# universky-SENSOR.net
KiCad netlist of a schematic drawn in Altium Designer
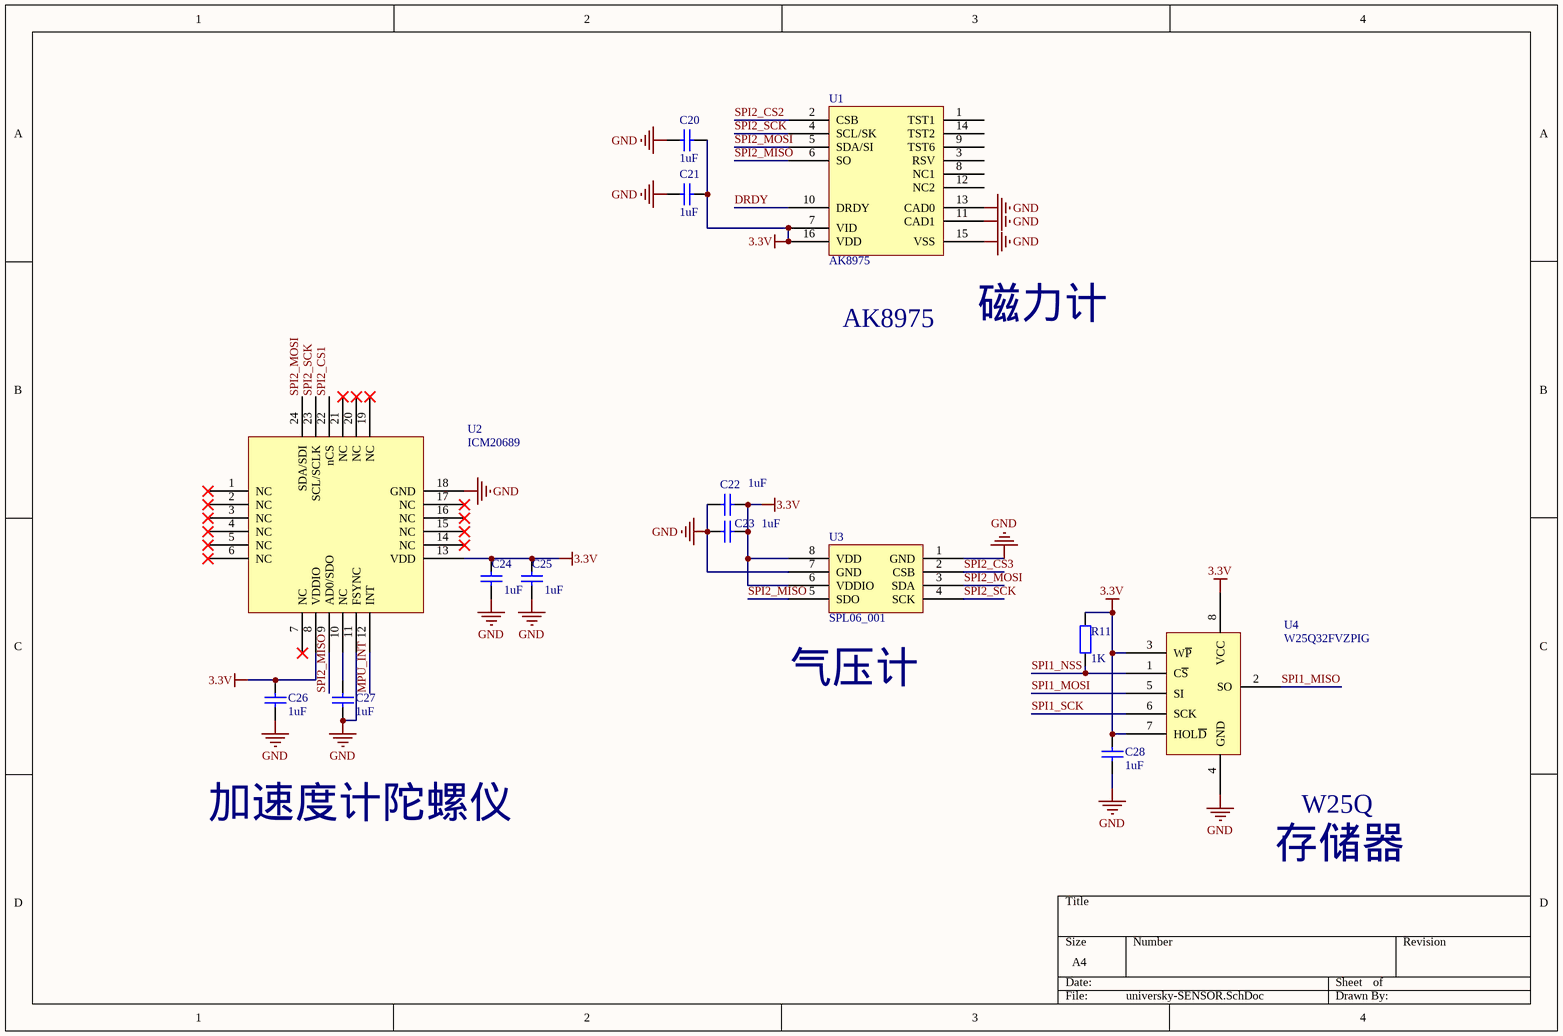
[diagram p0: universky-SENSOR.SchDoc]

(export (version "E")
  (design (tool "Eeschema 10.0.6"))
  (components
    (comp (ref "C20")
      (value "1uF")
      (footprint "0603_C")
      (description "Capacitor")
      (fields (field (name "Comment") "Cap") (field (name "PUBLISHER") "Altium Limited"))
      (libsource (lib "Miscellaneous Devices") (part "Cap"))
    )
    (comp (ref "C21")
      (value "1uF")
      (footprint "0603_C")
      (description "Capacitor")
      (fields (field (name "Comment") "Cap") (field (name "PUBLISHER") "Altium Limited"))
      (libsource (lib "Miscellaneous Devices") (part "Cap"))
    )
    (comp (ref "C22")
      (value "1uF")
      (footprint "0603_C")
      (description "Capacitor")
      (fields (field (name "Comment") "Cap") (field (name "PUBLISHER") "Altium Limited"))
      (libsource (lib "Miscellaneous Devices") (part "Cap"))
    )
    (comp (ref "C23")
      (value "1uF")
      (footprint "0603_C")
      (description "Capacitor")
      (fields (field (name "Comment") "Cap") (field (name "PUBLISHER") "Altium Limited"))
      (libsource (lib "Miscellaneous Devices") (part "Cap"))
    )
    (comp (ref "C24")
      (value "1uF")
      (footprint "0603_C")
      (description "Capacitor")
      (fields (field (name "Comment") "Cap") (field (name "PUBLISHER") "Altium Limited"))
      (libsource (lib "Miscellaneous Devices") (part "Cap"))
    )
    (comp (ref "C25")
      (value "1uF")
      (footprint "0603_C")
      (description "Capacitor")
      (fields (field (name "Comment") "Cap") (field (name "PUBLISHER") "Altium Limited"))
      (libsource (lib "Miscellaneous Devices") (part "Cap"))
    )
    (comp (ref "C26")
      (value "1uF")
      (footprint "0603_C")
      (description "Capacitor")
      (fields (field (name "Comment") "Cap") (field (name "PUBLISHER") "Altium Limited"))
      (libsource (lib "Miscellaneous Devices") (part "Cap"))
    )
    (comp (ref "C27")
      (value "1uF")
      (footprint "0603_C")
      (description "Capacitor")
      (fields (field (name "Comment") "Cap") (field (name "PUBLISHER") "Altium Limited"))
      (libsource (lib "Miscellaneous Devices") (part "Cap"))
    )
    (comp (ref "C28")
      (value "1uF")
      (footprint "0603_C")
      (description "Capacitor")
      (fields (field (name "Comment") "Cap") (field (name "PUBLISHER") "Altium Limited"))
      (libsource (lib "Miscellaneous Devices") (part "Cap"))
    )
    (comp (ref "R11")
      (value "1K")
      (footprint "0603_R")
      (description "Resistor")
      (fields (field (name "Comment") "Res2") (field (name "PUBLISHER") "Altium Limited"))
      (libsource (lib "Miscellaneous Devices") (part "Res2"))
    )
    (comp (ref "U1") (value "AK8975") (footprint "QFN_16") (libsource (lib "dx原理图库") (part "AK8975")))
    (comp (ref "U2") (value "ICM20689") (footprint "QFN_24") (libsource (lib "universea") (part "ICM20689")))
    (comp (ref "U3") (value "SPL06_001") (libsource (lib "universea") (part "SPL06_001")))
    (comp (ref "U4")
      (value "W25Q32FVZPIG")
      (footprint "WDFN_8")
      (libsource (lib "dx原理图库") (part "W25Q32FVZPIG"))
    )
  )
  (nets
    (net (code "1") (name "/DRDY") (class "Default")
      (node (ref "U1") (pin "10") (pinfunction "DRDY_10") (pintype "passive"))
    )
    (net (code "2") (name "/MPU_INT") (class "Default")
      (node (ref "U2") (pin "12") (pinfunction "INT_12") (pintype "passive"))
    )
    (net (code "3") (name "/SPI1_MISO") (class "Default")
      (node (ref "U4") (pin "2") (pinfunction "SO_2") (pintype "passive"))
    )
    (net (code "4") (name "/SPI1_MOSI") (class "Default")
      (node (ref "U4") (pin "5") (pinfunction "SI_5") (pintype "passive"))
    )
    (net (code "5") (name "/SPI1_NSS") (class "Default")
      (node (ref "R11") (pin "1") (pinfunction "1_1") (pintype "passive"))
      (node (ref "U4") (pin "1") (pinfunction "C~{S}_1") (pintype "passive"))
    )
    (net (code "6") (name "/SPI1_SCK") (class "Default")
      (node (ref "U4") (pin "6") (pinfunction "SCK_6") (pintype "passive"))
    )
    (net (code "7") (name "/SPI2_CS1") (class "Default")
      (node (ref "U2") (pin "22") (pinfunction "nCS_22") (pintype "passive"))
    )
    (net (code "8") (name "/SPI2_CS2") (class "Default")
      (node (ref "U1") (pin "2") (pinfunction "CSB_2") (pintype "passive"))
    )
    (net (code "9") (name "/SPI2_CS3") (class "Default")
      (node (ref "U3") (pin "2") (pinfunction "CSB_2") (pintype "passive"))
    )
    (net (code "10") (name "/SPI2_MISO") (class "Default")
      (node (ref "U1") (pin "6") (pinfunction "SO_6") (pintype "passive"))
      (node (ref "U2") (pin "9") (pinfunction "AD0/SDO_9") (pintype "passive"))
      (node (ref "U3") (pin "5") (pinfunction "SDO_5") (pintype "passive"))
    )
    (net (code "11") (name "/SPI2_MOSI") (class "Default")
      (node (ref "U1") (pin "5") (pinfunction "SDA/SI_5") (pintype "passive"))
      (node (ref "U2") (pin "24") (pinfunction "SDA/SDI_24") (pintype "passive"))
      (node (ref "U3") (pin "3") (pinfunction "SDA_3") (pintype "passive"))
    )
    (net (code "12") (name "/SPI2_SCK") (class "Default")
      (node (ref "U1") (pin "4") (pinfunction "SCL/SK_4") (pintype "passive"))
      (node (ref "U2") (pin "23") (pinfunction "SCL/SCLK_23") (pintype "passive"))
      (node (ref "U3") (pin "4") (pinfunction "SCK_4") (pintype "passive"))
    )
    (net (code "13") (name "3.3V") (class "Default")
      (node (ref "C20") (pin "1") (pinfunction "1_1") (pintype "passive"))
      (node (ref "C21") (pin "1") (pinfunction "1_1") (pintype "passive"))
      (node (ref "C22") (pin "1") (pinfunction "1_1") (pintype "passive"))
      (node (ref "C23") (pin "1") (pinfunction "1_1") (pintype "passive"))
      (node (ref "C24") (pin "2") (pinfunction "2_2") (pintype "passive"))
      (node (ref "C25") (pin "2") (pinfunction "2_2") (pintype "passive"))
      (node (ref "C26") (pin "2") (pinfunction "2_2") (pintype "passive"))
      (node (ref "C28") (pin "1") (pinfunction "1_1") (pintype "passive"))
      (node (ref "R11") (pin "2") (pinfunction "2_2") (pintype "passive"))
      (node (ref "U1") (pin "16") (pinfunction "VDD_16") (pintype "passive"))
      (node (ref "U1") (pin "7") (pinfunction "VID_7") (pintype "passive"))
      (node (ref "U2") (pin "13") (pinfunction "VDD_13") (pintype "passive"))
      (node (ref "U2") (pin "8") (pinfunction "VDDIO_8") (pintype "passive"))
      (node (ref "U3") (pin "6") (pinfunction "VDDIO_6") (pintype "passive"))
      (node (ref "U3") (pin "8") (pinfunction "VDD_8") (pintype "passive"))
      (node (ref "U4") (pin "3") (pinfunction "W~{P}_3") (pintype "passive"))
      (node (ref "U4") (pin "7") (pinfunction "HOL~{D}_7") (pintype "passive"))
      (node (ref "U4") (pin "8") (pinfunction "VCC_8") (pintype "passive"))
    )
    (net (code "14") (name "GND") (class "Default")
      (node (ref "C20") (pin "2") (pinfunction "2_2") (pintype "passive"))
      (node (ref "C21") (pin "2") (pinfunction "2_2") (pintype "passive"))
      (node (ref "C22") (pin "2") (pinfunction "2_2") (pintype "passive"))
      (node (ref "C23") (pin "2") (pinfunction "2_2") (pintype "passive"))
      (node (ref "C24") (pin "1") (pinfunction "1_1") (pintype "passive"))
      (node (ref "C25") (pin "1") (pinfunction "1_1") (pintype "passive"))
      (node (ref "C26") (pin "1") (pinfunction "1_1") (pintype "passive"))
      (node (ref "C27") (pin "1") (pinfunction "1_1") (pintype "passive"))
      (node (ref "C28") (pin "2") (pinfunction "2_2") (pintype "passive"))
      (node (ref "U1") (pin "11") (pinfunction "CAD1_11") (pintype "passive"))
      (node (ref "U1") (pin "13") (pinfunction "CAD0_13") (pintype "passive"))
      (node (ref "U1") (pin "15") (pinfunction "VSS_15") (pintype "passive"))
      (node (ref "U2") (pin "11") (pinfunction "FSYNC_11") (pintype "passive"))
      (node (ref "U2") (pin "18") (pinfunction "GND_18") (pintype "passive"))
      (node (ref "U3") (pin "1") (pinfunction "GND_1") (pintype "passive"))
      (node (ref "U3") (pin "7") (pinfunction "GND_7") (pintype "passive"))
      (node (ref "U4") (pin "4") (pinfunction "GND_4") (pintype "passive"))
    )
    (net (code "15") (name "Net-(C27-Pad2)") (class "Default")
      (node (ref "C27") (pin "2") (pinfunction "2_2") (pintype "passive"))
      (node (ref "U2") (pin "10") (pinfunction "NC_10") (pintype "passive"))
    )
    (net (code "16") (name "unconnected-(U1-NC1-Pad8)") (class "Default")
      (node (ref "U1") (pin "8") (pinfunction "NC1_8") (pintype "passive"))
    )
    (net (code "17") (name "unconnected-(U1-NC2-Pad12)") (class "Default")
      (node (ref "U1") (pin "12") (pinfunction "NC2_12") (pintype "passive"))
    )
    (net (code "18") (name "unconnected-(U1-RSV-Pad3)") (class "Default")
      (node (ref "U1") (pin "3") (pinfunction "RSV_3") (pintype "passive"))
    )
    (net (code "19") (name "unconnected-(U1-TST1-Pad1)") (class "Default")
      (node (ref "U1") (pin "1") (pinfunction "TST1_1") (pintype "passive"))
    )
    (net (code "20") (name "unconnected-(U1-TST2-Pad14)") (class "Default")
      (node (ref "U1") (pin "14") (pinfunction "TST2_14") (pintype "passive"))
    )
    (net (code "21") (name "unconnected-(U1-TST6-Pad9)") (class "Default")
      (node (ref "U1") (pin "9") (pinfunction "TST6_9") (pintype "passive"))
    )
    (net (code "22") (name "unconnected-(U2-NC-Pad1)") (class "Default")
      (node (ref "U2") (pin "1") (pinfunction "NC_1") (pintype "passive+no_connect"))
    )
    (net (code "23") (name "unconnected-(U2-NC-Pad2)") (class "Default")
      (node (ref "U2") (pin "2") (pinfunction "NC_2") (pintype "passive+no_connect"))
    )
    (net (code "24") (name "unconnected-(U2-NC-Pad3)") (class "Default")
      (node (ref "U2") (pin "3") (pinfunction "NC_3") (pintype "passive+no_connect"))
    )
    (net (code "25") (name "unconnected-(U2-NC-Pad4)") (class "Default")
      (node (ref "U2") (pin "4") (pinfunction "NC_4") (pintype "passive+no_connect"))
    )
    (net (code "26") (name "unconnected-(U2-NC-Pad5)") (class "Default")
      (node (ref "U2") (pin "5") (pinfunction "NC_5") (pintype "passive+no_connect"))
    )
    (net (code "27") (name "unconnected-(U2-NC-Pad6)") (class "Default")
      (node (ref "U2") (pin "6") (pinfunction "NC_6") (pintype "passive+no_connect"))
    )
    (net (code "28") (name "unconnected-(U2-NC-Pad7)") (class "Default")
      (node (ref "U2") (pin "7") (pinfunction "NC_7") (pintype "passive+no_connect"))
    )
    (net (code "29") (name "unconnected-(U2-NC-Pad14)") (class "Default")
      (node (ref "U2") (pin "14") (pinfunction "NC_14") (pintype "passive+no_connect"))
    )
    (net (code "30") (name "unconnected-(U2-NC-Pad15)") (class "Default")
      (node (ref "U2") (pin "15") (pinfunction "NC_15") (pintype "passive+no_connect"))
    )
    (net (code "31") (name "unconnected-(U2-NC-Pad16)") (class "Default")
      (node (ref "U2") (pin "16") (pinfunction "NC_16") (pintype "passive+no_connect"))
    )
    (net (code "32") (name "unconnected-(U2-NC-Pad17)") (class "Default")
      (node (ref "U2") (pin "17") (pinfunction "NC_17") (pintype "passive+no_connect"))
    )
    (net (code "33") (name "unconnected-(U2-NC-Pad19)") (class "Default")
      (node (ref "U2") (pin "19") (pinfunction "NC_19") (pintype "passive+no_connect"))
    )
    (net (code "34") (name "unconnected-(U2-NC-Pad20)") (class "Default")
      (node (ref "U2") (pin "20") (pinfunction "NC_20") (pintype "passive+no_connect"))
    )
    (net (code "35") (name "unconnected-(U2-NC-Pad21)") (class "Default")
      (node (ref "U2") (pin "21") (pinfunction "NC_21") (pintype "passive+no_connect"))
    )
  )
)
